# SlipSensorEvalBoard.net
KiCad netlist of a schematic drawn in Altium Designer
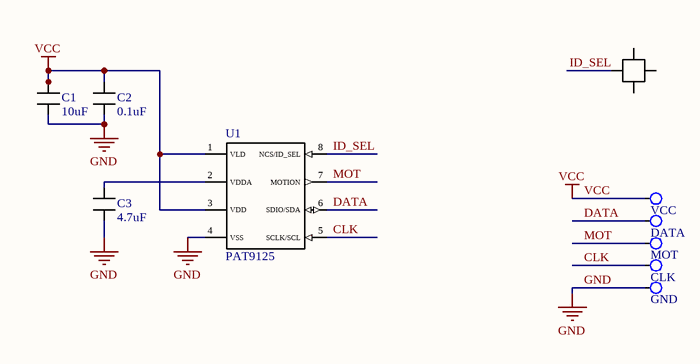
[diagram p0: SlipSensorEvalBoard.SchDoc]

(export (version "E")
  (design (tool "Eeschema 10.0.6"))
  (components
    (comp (ref "C1")
      (value "10uF")
      (footprint "CAPC0816X55N")
      (description "10µF ±20% 2.5V Ceramic Capacitor X6S 0306 (0816 Metric)")
      (fields (field (name "MF") "Taiyo Yuden") (field (name "DIGI-KEY_PART_NUMBER") "587-5158-1-ND"))
      (libsource (lib "Limbo") (part "cap_10uF"))
    )
    (comp (ref "C2")
      (value "0.1uF")
      (footprint "Limbo:cap_0.1uF")
      (description "0.1µF ±20% 6.3V Ceramic Capacitor X7S 0204 (0510 Metric)")
      (fields (field (name "MP") "JWK105C7104MP-F") (field (name "MF") "Taiyo Yuden"))
      (libsource (lib "Limbo") (part "cap_0.1uF"))
    )
    (comp (ref "C3")
      (value "4.7uF")
      (footprint "CAPC0816X55N")
      (description "4.7µF ±20% 4V Ceramic Capacitor X6S 0306 (0816 Metric)")
      (fields (field (name "DIGI-KEY_PART_NUMBER") "587-5162-1-ND") (field (name "MP") "AWK107C6475MV-T"))
      (libsource (lib "Limbo") (part "cap_4.7uF"))
    )
    (comp (ref "CLK") (value "Holepad") (footprint "Holepad") (libsource (lib "Limbo") (part "Holepad")))
    (comp (ref "DATA") (value "Holepad") (footprint "Holepad") (libsource (lib "Limbo") (part "Holepad")))
    (comp (ref "GND") (value "Holepad") (footprint "Holepad") (libsource (lib "Limbo") (part "Holepad")))
    (comp (ref "ID_SEL")
      (value "Wirepad")
      (footprint "Wirepad")
      (description "SMD pad to solder a wire straight onto the PCB.")
      (libsource (lib "Limbo") (part "Wirepad"))
    )
    (comp (ref "MOT") (value "Holepad") (footprint "Holepad") (libsource (lib "Limbo") (part "Holepad")))
    (comp (ref "U1")
      (value "Optical Navigation Sensor")
      (footprint "PAT9125")
      (description "Miniature Optical Navigation Chip")
      (fields (field (name "NAME") "PAT9125"))
      (libsource (lib "Limbo") (part "PAT9125"))
    )
    (comp (ref "VCC") (value "Holepad") (footprint "Holepad") (libsource (lib "Limbo") (part "Holepad")))
  )
  (nets
    (net (code "1") (name "/CLK") (class "Default")
      (node (ref "CLK") (pin "1") (pinfunction "1_1") (pintype "passive"))
      (node (ref "U1") (pin "5") (pinfunction "SCLK/SCL_5") (pintype "input"))
    )
    (net (code "2") (name "/DATA") (class "Default")
      (node (ref "DATA") (pin "1") (pinfunction "1_1") (pintype "passive"))
      (node (ref "U1") (pin "6") (pinfunction "SDIO/SDA_6") (pintype "bidirectional"))
    )
    (net (code "3") (name "/ID_SEL") (class "Default")
      (node (ref "ID_SEL") (pin "2") (pinfunction "Q?_2") (pintype "passive"))
      (node (ref "U1") (pin "8") (pinfunction "NCS/ID_SEL_8") (pintype "input"))
    )
    (net (code "4") (name "/MOT") (class "Default")
      (node (ref "MOT") (pin "1") (pinfunction "1_1") (pintype "passive"))
      (node (ref "U1") (pin "7") (pinfunction "MOTION_7") (pintype "output"))
    )
    (net (code "5") (name "GND") (class "Default")
      (node (ref "C1") (pin "1") (pinfunction "1_1") (pintype "passive"))
      (node (ref "C2") (pin "1") (pinfunction "1_1") (pintype "passive"))
      (node (ref "C3") (pin "1") (pinfunction "1_1") (pintype "passive"))
      (node (ref "GND") (pin "1") (pinfunction "1_1") (pintype "passive"))
      (node (ref "U1") (pin "4") (pinfunction "VSS_4") (pintype "power_in"))
    )
    (net (code "6") (name "Net-(U1-VDDA)") (class "Default")
      (node (ref "C3") (pin "2") (pinfunction "2_2") (pintype "passive"))
      (node (ref "U1") (pin "2") (pinfunction "VDDA_2") (pintype "power_in"))
    )
    (net (code "7") (name "VCC") (class "Default")
      (node (ref "C1") (pin "2") (pinfunction "2_2") (pintype "passive"))
      (node (ref "C2") (pin "2") (pinfunction "2_2") (pintype "passive"))
      (node (ref "U1") (pin "1") (pinfunction "VLD_1") (pintype "power_in"))
      (node (ref "U1") (pin "3") (pinfunction "VDD_3") (pintype "power_in"))
      (node (ref "VCC") (pin "1") (pinfunction "1_1") (pintype "passive"))
    )
    (net (code "8") (name "unconnected-(ID_SEL-Q?-Pad1)") (class "Default")
      (node (ref "ID_SEL") (pin "1") (pinfunction "Q?_1") (pintype "passive"))
    )
    (net (code "9") (name "unconnected-(ID_SEL-Q?-Pad3)") (class "Default")
      (node (ref "ID_SEL") (pin "3") (pinfunction "Q?_3") (pintype "passive"))
    )
    (net (code "10") (name "unconnected-(ID_SEL-Q?-Pad4)") (class "Default")
      (node (ref "ID_SEL") (pin "4") (pinfunction "Q?_4") (pintype "passive"))
    )
  )
)
